# FeatherProto-V3_0.net
KiCad netlist of a schematic drawn in EAGLE
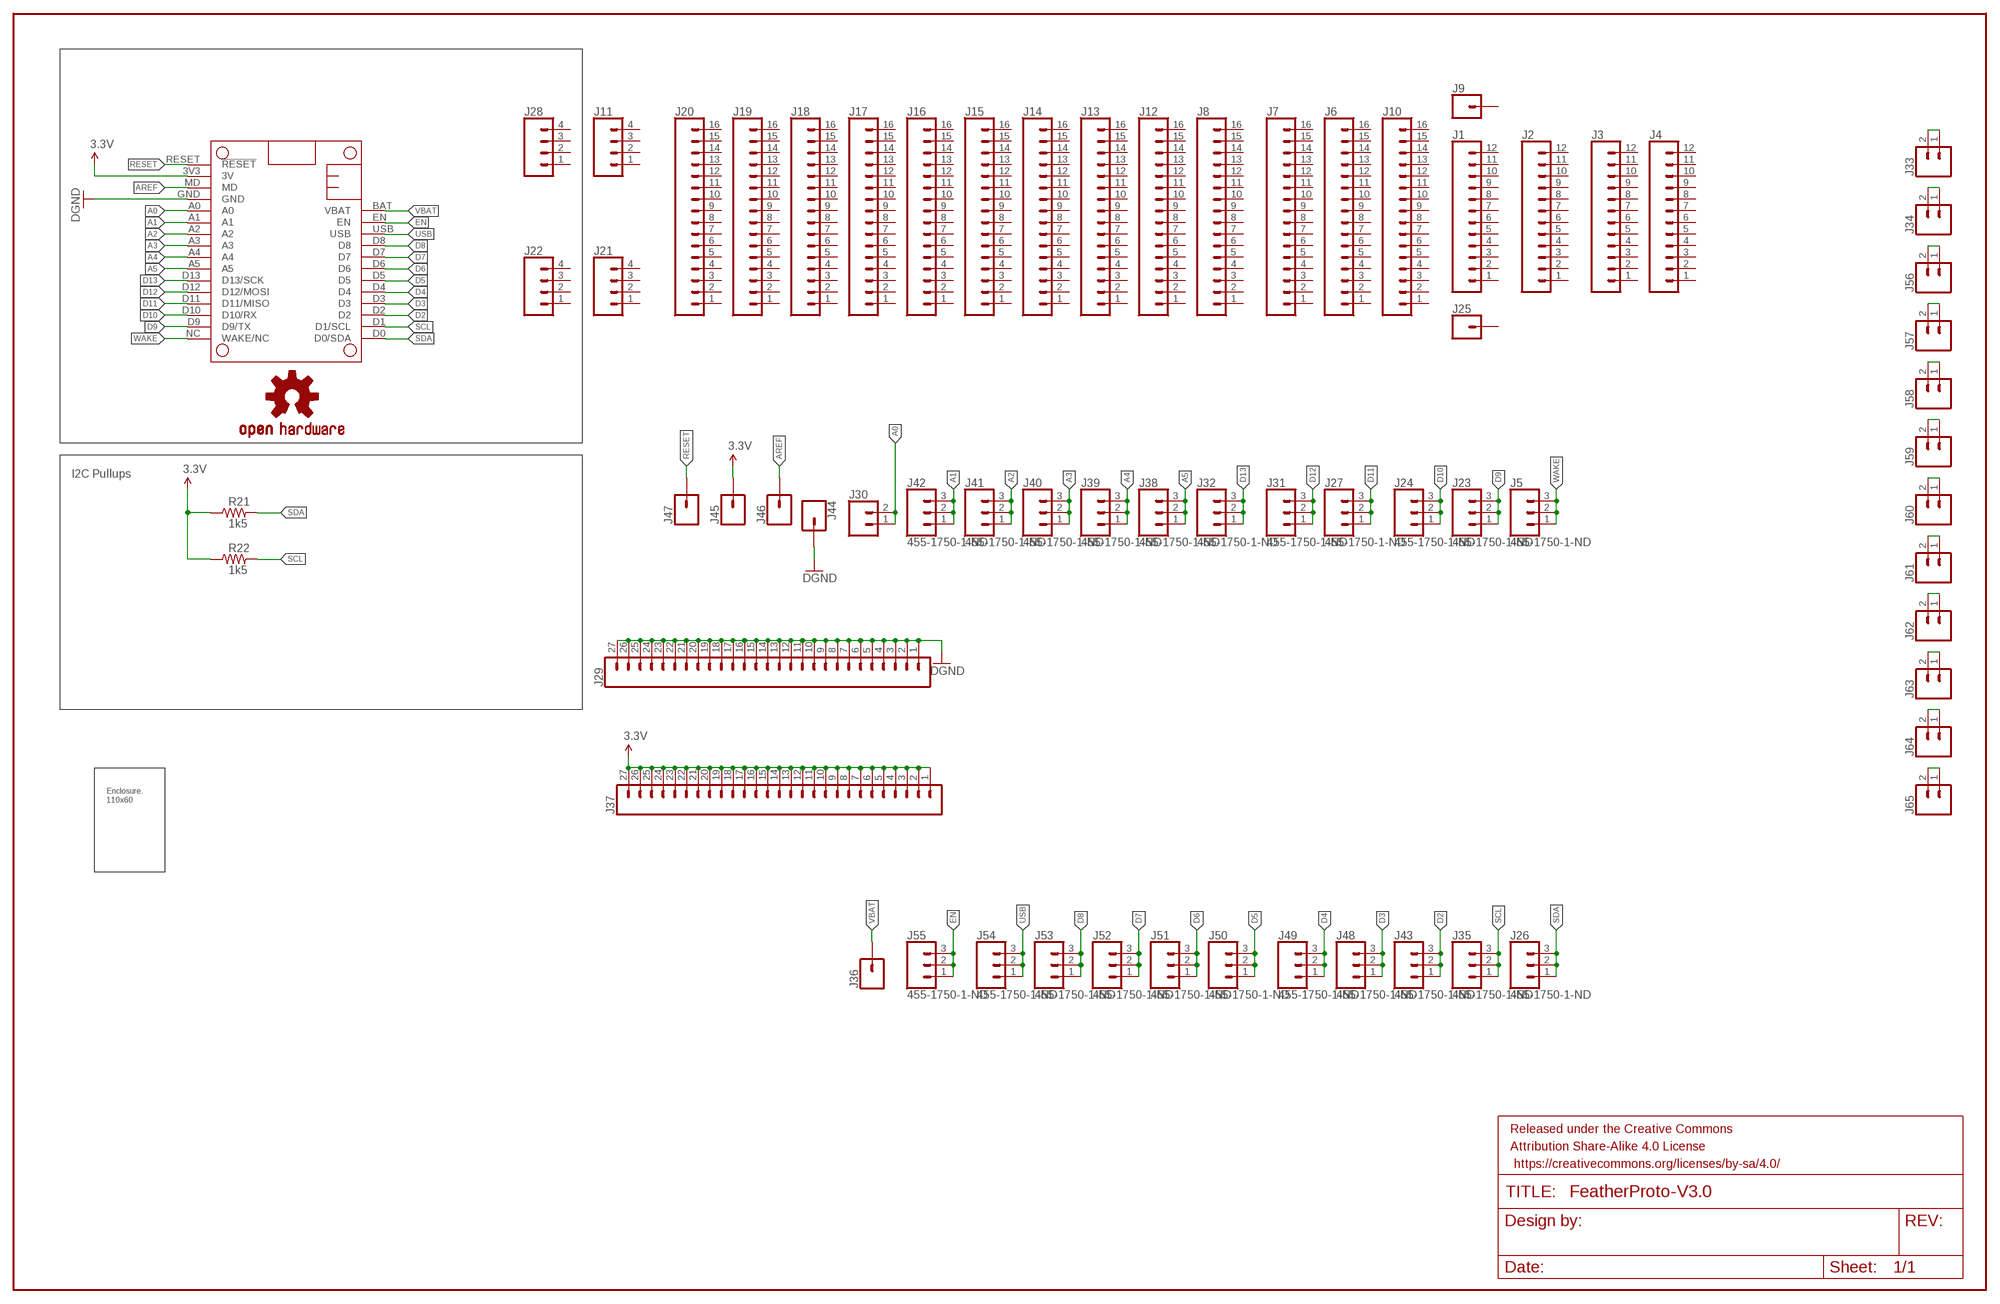
[diagram p0: schematic, sheet 1]

(export (version "E")
  (design (tool "Eeschema 10.0.6"))
  (components
    (comp (ref "FRAME2")
      (value "FRAME-LEDGER")
      (footprint "eagle-import:CREATIVE_COMMONS")
      (libsource (lib "eagle-import") (part "FRAME-LEDGER"))
    )
    (comp (ref "J1")
      (value "CONN_12NO_SILK")
      (footprint "eagle-import:1X12_NO_SILK")
      (libsource (lib "eagle-import") (part "CONN_12NO_SILK"))
    )
    (comp (ref "J2")
      (value "CONN_12NO_SILK")
      (footprint "eagle-import:1X12_NO_SILK")
      (libsource (lib "eagle-import") (part "CONN_12NO_SILK"))
    )
    (comp (ref "J3")
      (value "CONN_12NO_SILK")
      (footprint "eagle-import:1X12_NO_SILK")
      (libsource (lib "eagle-import") (part "CONN_12NO_SILK"))
    )
    (comp (ref "J4")
      (value "CONN_12NO_SILK")
      (footprint "eagle-import:1X12_NO_SILK")
      (libsource (lib "eagle-import") (part "CONN_12NO_SILK"))
    )
    (comp (ref "J5")
      (value "455-1750-1-ND")
      (footprint "eagle-import:1X03")
      (libsource (lib "eagle-import") (part "CONN_03"))
    )
    (comp (ref "J6")
      (value "CONN_161X16_NO_SILK")
      (footprint "eagle-import:1X16_NO_SILK")
      (libsource (lib "eagle-import") (part "CONN_161X16_NO_SILK"))
    )
    (comp (ref "J7")
      (value "CONN_161X16_NO_SILK")
      (footprint "eagle-import:1X16_NO_SILK")
      (libsource (lib "eagle-import") (part "CONN_161X16_NO_SILK"))
    )
    (comp (ref "J8")
      (value "CONN_161X16_NO_SILK")
      (footprint "eagle-import:1X16_NO_SILK")
      (libsource (lib "eagle-import") (part "CONN_161X16_NO_SILK"))
    )
    (comp (ref "J9")
      (value "CONN_01PTH_NO_SILK_YES_STOP")
      (footprint "eagle-import:1X01_NO_SILK")
      (libsource (lib "eagle-import") (part "CONN_01PTH_NO_SILK_YES_STOP"))
    )
    (comp (ref "J10")
      (value "CONN_161X16_NO_SILK")
      (footprint "eagle-import:1X16_NO_SILK")
      (libsource (lib "eagle-import") (part "CONN_161X16_NO_SILK"))
    )
    (comp (ref "J11")
      (value "CONN_041X04_NO_SILK")
      (footprint "eagle-import:1X04_NO_SILK")
      (libsource (lib "eagle-import") (part "CONN_041X04_NO_SILK"))
    )
    (comp (ref "J12")
      (value "CONN_161X16_NO_SILK")
      (footprint "eagle-import:1X16_NO_SILK")
      (libsource (lib "eagle-import") (part "CONN_161X16_NO_SILK"))
    )
    (comp (ref "J13")
      (value "CONN_161X16_NO_SILK")
      (footprint "eagle-import:1X16_NO_SILK")
      (libsource (lib "eagle-import") (part "CONN_161X16_NO_SILK"))
    )
    (comp (ref "J14")
      (value "CONN_161X16_NO_SILK")
      (footprint "eagle-import:1X16_NO_SILK")
      (libsource (lib "eagle-import") (part "CONN_161X16_NO_SILK"))
    )
    (comp (ref "J15")
      (value "CONN_161X16_NO_SILK")
      (footprint "eagle-import:1X16_NO_SILK")
      (libsource (lib "eagle-import") (part "CONN_161X16_NO_SILK"))
    )
    (comp (ref "J16")
      (value "CONN_161X16_NO_SILK")
      (footprint "eagle-import:1X16_NO_SILK")
      (libsource (lib "eagle-import") (part "CONN_161X16_NO_SILK"))
    )
    (comp (ref "J17")
      (value "CONN_161X16_NO_SILK")
      (footprint "eagle-import:1X16_NO_SILK")
      (libsource (lib "eagle-import") (part "CONN_161X16_NO_SILK"))
    )
    (comp (ref "J18")
      (value "CONN_161X16_NO_SILK")
      (footprint "eagle-import:1X16_NO_SILK")
      (libsource (lib "eagle-import") (part "CONN_161X16_NO_SILK"))
    )
    (comp (ref "J19")
      (value "CONN_161X16_NO_SILK")
      (footprint "eagle-import:1X16_NO_SILK")
      (libsource (lib "eagle-import") (part "CONN_161X16_NO_SILK"))
    )
    (comp (ref "J20")
      (value "CONN_161X16_NO_SILK")
      (footprint "eagle-import:1X16_NO_SILK")
      (libsource (lib "eagle-import") (part "CONN_161X16_NO_SILK"))
    )
    (comp (ref "J21")
      (value "CONN_041X04_NO_SILK")
      (footprint "eagle-import:1X04_NO_SILK")
      (libsource (lib "eagle-import") (part "CONN_041X04_NO_SILK"))
    )
    (comp (ref "J22")
      (value "CONN_041X04_NO_SILK")
      (footprint "eagle-import:1X04_NO_SILK")
      (libsource (lib "eagle-import") (part "CONN_041X04_NO_SILK"))
    )
    (comp (ref "J23")
      (value "455-1750-1-ND")
      (footprint "eagle-import:1X03")
      (libsource (lib "eagle-import") (part "CONN_03"))
    )
    (comp (ref "J24")
      (value "455-1750-1-ND")
      (footprint "eagle-import:1X03")
      (libsource (lib "eagle-import") (part "CONN_03"))
    )
    (comp (ref "J25")
      (value "CONN_01PTH_NO_SILK_YES_STOP")
      (footprint "eagle-import:1X01_NO_SILK")
      (libsource (lib "eagle-import") (part "CONN_01PTH_NO_SILK_YES_STOP"))
    )
    (comp (ref "J26")
      (value "455-1750-1-ND")
      (footprint "eagle-import:1X03")
      (libsource (lib "eagle-import") (part "CONN_03"))
    )
    (comp (ref "J27")
      (value "455-1750-1-ND")
      (footprint "eagle-import:1X03")
      (libsource (lib "eagle-import") (part "CONN_03"))
    )
    (comp (ref "J28")
      (value "CONN_041X04_NO_SILK")
      (footprint "eagle-import:1X04_NO_SILK")
      (libsource (lib "eagle-import") (part "CONN_041X04_NO_SILK"))
    )
    (comp (ref "J29")
      (value "CONN_27")
      (footprint "eagle-import:1X27")
      (libsource (lib "eagle-import") (part "CONN_27"))
    )
    (comp (ref "J30")
      (value "CONN_02")
      (footprint "eagle-import:1X02")
      (libsource (lib "eagle-import") (part "CONN_02"))
    )
    (comp (ref "J31")
      (value "455-1750-1-ND")
      (footprint "eagle-import:1X03")
      (libsource (lib "eagle-import") (part "CONN_03"))
    )
    (comp (ref "J32")
      (value "455-1750-1-ND")
      (footprint "eagle-import:1X03")
      (libsource (lib "eagle-import") (part "CONN_03"))
    )
    (comp (ref "J33")
      (value "CONN_02")
      (footprint "eagle-import:1X02")
      (libsource (lib "eagle-import") (part "CONN_02"))
    )
    (comp (ref "J34")
      (value "CONN_02")
      (footprint "eagle-import:1X02")
      (libsource (lib "eagle-import") (part "CONN_02"))
    )
    (comp (ref "J35")
      (value "455-1750-1-ND")
      (footprint "eagle-import:1X03")
      (libsource (lib "eagle-import") (part "CONN_03"))
    )
    (comp (ref "J36")
      (value "CONN_01PTH_NO_SILK_YES_STOP")
      (footprint "eagle-import:1X01_NO_SILK")
      (libsource (lib "eagle-import") (part "CONN_01PTH_NO_SILK_YES_STOP"))
    )
    (comp (ref "J37")
      (value "CONN_27")
      (footprint "eagle-import:1X27")
      (libsource (lib "eagle-import") (part "CONN_27"))
    )
    (comp (ref "J38")
      (value "455-1750-1-ND")
      (footprint "eagle-import:1X03")
      (libsource (lib "eagle-import") (part "CONN_03"))
    )
    (comp (ref "J39")
      (value "455-1750-1-ND")
      (footprint "eagle-import:1X03")
      (libsource (lib "eagle-import") (part "CONN_03"))
    )
    (comp (ref "J40")
      (value "455-1750-1-ND")
      (footprint "eagle-import:1X03")
      (libsource (lib "eagle-import") (part "CONN_03"))
    )
    (comp (ref "J41")
      (value "455-1750-1-ND")
      (footprint "eagle-import:1X03")
      (libsource (lib "eagle-import") (part "CONN_03"))
    )
    (comp (ref "J42")
      (value "455-1750-1-ND")
      (footprint "eagle-import:1X03")
      (libsource (lib "eagle-import") (part "CONN_03"))
    )
    (comp (ref "J43")
      (value "455-1750-1-ND")
      (footprint "eagle-import:1X03")
      (libsource (lib "eagle-import") (part "CONN_03"))
    )
    (comp (ref "J44")
      (value "CONN_01PTH_NO_SILK_YES_STOP")
      (footprint "eagle-import:1X01_NO_SILK")
      (libsource (lib "eagle-import") (part "CONN_01PTH_NO_SILK_YES_STOP"))
    )
    (comp (ref "J45")
      (value "CONN_01PTH_NO_SILK_YES_STOP")
      (footprint "eagle-import:1X01_NO_SILK")
      (libsource (lib "eagle-import") (part "CONN_01PTH_NO_SILK_YES_STOP"))
    )
    (comp (ref "J46")
      (value "CONN_01PTH_NO_SILK_YES_STOP")
      (footprint "eagle-import:1X01_NO_SILK")
      (libsource (lib "eagle-import") (part "CONN_01PTH_NO_SILK_YES_STOP"))
    )
    (comp (ref "J47")
      (value "CONN_01PTH_NO_SILK_YES_STOP")
      (footprint "eagle-import:1X01_NO_SILK")
      (libsource (lib "eagle-import") (part "CONN_01PTH_NO_SILK_YES_STOP"))
    )
    (comp (ref "J48")
      (value "455-1750-1-ND")
      (footprint "eagle-import:1X03")
      (libsource (lib "eagle-import") (part "CONN_03"))
    )
    (comp (ref "J49")
      (value "455-1750-1-ND")
      (footprint "eagle-import:1X03")
      (libsource (lib "eagle-import") (part "CONN_03"))
    )
    (comp (ref "J50")
      (value "455-1750-1-ND")
      (footprint "eagle-import:1X03")
      (libsource (lib "eagle-import") (part "CONN_03"))
    )
    (comp (ref "J51")
      (value "455-1750-1-ND")
      (footprint "eagle-import:1X03")
      (libsource (lib "eagle-import") (part "CONN_03"))
    )
    (comp (ref "J52")
      (value "455-1750-1-ND")
      (footprint "eagle-import:1X03")
      (libsource (lib "eagle-import") (part "CONN_03"))
    )
    (comp (ref "J53")
      (value "455-1750-1-ND")
      (footprint "eagle-import:1X03")
      (libsource (lib "eagle-import") (part "CONN_03"))
    )
    (comp (ref "J54")
      (value "455-1750-1-ND")
      (footprint "eagle-import:1X03")
      (libsource (lib "eagle-import") (part "CONN_03"))
    )
    (comp (ref "J55")
      (value "455-1750-1-ND")
      (footprint "eagle-import:1X03")
      (libsource (lib "eagle-import") (part "CONN_03"))
    )
    (comp (ref "J56")
      (value "CONN_02")
      (footprint "eagle-import:1X02")
      (libsource (lib "eagle-import") (part "CONN_02"))
    )
    (comp (ref "J57")
      (value "CONN_02")
      (footprint "eagle-import:1X02")
      (libsource (lib "eagle-import") (part "CONN_02"))
    )
    (comp (ref "J58")
      (value "CONN_02")
      (footprint "eagle-import:1X02")
      (libsource (lib "eagle-import") (part "CONN_02"))
    )
    (comp (ref "J59")
      (value "CONN_02")
      (footprint "eagle-import:1X02")
      (libsource (lib "eagle-import") (part "CONN_02"))
    )
    (comp (ref "J60")
      (value "CONN_02")
      (footprint "eagle-import:1X02")
      (libsource (lib "eagle-import") (part "CONN_02"))
    )
    (comp (ref "J61")
      (value "CONN_02")
      (footprint "eagle-import:1X02")
      (libsource (lib "eagle-import") (part "CONN_02"))
    )
    (comp (ref "J62")
      (value "CONN_02")
      (footprint "eagle-import:1X02")
      (libsource (lib "eagle-import") (part "CONN_02"))
    )
    (comp (ref "J63")
      (value "CONN_02")
      (footprint "eagle-import:1X02")
      (libsource (lib "eagle-import") (part "CONN_02"))
    )
    (comp (ref "J64")
      (value "CONN_02")
      (footprint "eagle-import:1X02")
      (libsource (lib "eagle-import") (part "CONN_02"))
    )
    (comp (ref "J65")
      (value "CONN_02")
      (footprint "eagle-import:1X02")
      (libsource (lib "eagle-import") (part "CONN_02"))
    )
    (comp (ref "LOGO1")
      (value "OSHW-LOGOM")
      (footprint "eagle-import:OSHW-LOGO-M")
      (libsource (lib "eagle-import") (part "OSHW-LOGOM"))
    )
    (comp (ref "MS1")
      (value "XENONA")
      (footprint "eagle-import:XENON_BREAKOUT_A")
      (libsource (lib "eagle-import") (part "XENONA"))
    )
    (comp (ref "R21")
      (value "1k5")
      (footprint "eagle-import:0805")
      (libsource (lib "eagle-import") (part "RESISTOR0805"))
    )
    (comp (ref "R22")
      (value "1k5")
      (footprint "eagle-import:0805")
      (libsource (lib "eagle-import") (part "RESISTOR0805"))
    )
    (comp (ref "U$1")
      (value "CAMDENBOSS-ENCLOSURE-110X60BOTH-EXTENDED-WIDE")
      (footprint "eagle-import:CAMDENBOSS_ENCLOSURE_110X60_WIDE_EXTENDED")
      (libsource (lib "eagle-import") (part "CAMDENBOSS-ENCLOSURE-110X60BOTH-EXTENDED-WIDE"))
    )
  )
  (nets
    (net (code "1") (name "3.3V") (class "Default")
      (node (ref "J37") (pin "1") (pinfunction "1_1") (pintype "passive"))
      (node (ref "J37") (pin "10") (pinfunction "10_10") (pintype "passive"))
      (node (ref "J37") (pin "11") (pinfunction "11_11") (pintype "passive"))
      (node (ref "J37") (pin "12") (pinfunction "12_12") (pintype "passive"))
      (node (ref "J37") (pin "13") (pinfunction "13_13") (pintype "passive"))
      (node (ref "J37") (pin "14") (pinfunction "14_14") (pintype "passive"))
      (node (ref "J37") (pin "15") (pinfunction "15_15") (pintype "passive"))
      (node (ref "J37") (pin "16") (pinfunction "16_16") (pintype "passive"))
      (node (ref "J37") (pin "17") (pinfunction "17_17") (pintype "passive"))
      (node (ref "J37") (pin "18") (pinfunction "18_18") (pintype "passive"))
      (node (ref "J37") (pin "19") (pinfunction "19_19") (pintype "passive"))
      (node (ref "J37") (pin "2") (pinfunction "2_2") (pintype "passive"))
      (node (ref "J37") (pin "20") (pinfunction "20_20") (pintype "passive"))
      (node (ref "J37") (pin "21") (pinfunction "21_21") (pintype "passive"))
      (node (ref "J37") (pin "22") (pinfunction "22_22") (pintype "passive"))
      (node (ref "J37") (pin "23") (pinfunction "23_23") (pintype "passive"))
      (node (ref "J37") (pin "24") (pinfunction "24_24") (pintype "passive"))
      (node (ref "J37") (pin "25") (pinfunction "25_25") (pintype "passive"))
      (node (ref "J37") (pin "26") (pinfunction "26_26") (pintype "passive"))
      (node (ref "J37") (pin "27") (pinfunction "27_27") (pintype "passive"))
      (node (ref "J37") (pin "3") (pinfunction "3_3") (pintype "passive"))
      (node (ref "J37") (pin "4") (pinfunction "4_4") (pintype "passive"))
      (node (ref "J37") (pin "5") (pinfunction "5_5") (pintype "passive"))
      (node (ref "J37") (pin "6") (pinfunction "6_6") (pintype "passive"))
      (node (ref "J37") (pin "7") (pinfunction "7_7") (pintype "passive"))
      (node (ref "J37") (pin "8") (pinfunction "8_8") (pintype "passive"))
      (node (ref "J37") (pin "9") (pinfunction "9_9") (pintype "passive"))
      (node (ref "J45") (pin "1") (pinfunction "1_1") (pintype "passive"))
      (node (ref "MS1") (pin "3V3") (pinfunction "3V_3V3") (pintype "power_in"))
      (node (ref "R21") (pin "1") (pinfunction "1_1") (pintype "passive"))
      (node (ref "R22") (pin "1") (pinfunction "1_1") (pintype "passive"))
    )
    (net (code "2") (name "A0") (class "Default")
      (node (ref "J30") (pin "1") (pinfunction "1_1") (pintype "passive"))
      (node (ref "J30") (pin "2") (pinfunction "2_2") (pintype "passive"))
      (node (ref "MS1") (pin "A0") (pinfunction "A0_A0") (pintype "bidirectional"))
    )
    (net (code "3") (name "A1") (class "Default")
      (node (ref "J42") (pin "1") (pinfunction "1_1") (pintype "passive"))
      (node (ref "J42") (pin "2") (pinfunction "2_2") (pintype "passive"))
      (node (ref "J42") (pin "3") (pinfunction "3_3") (pintype "passive"))
      (node (ref "MS1") (pin "A1") (pinfunction "A1_A1") (pintype "bidirectional"))
    )
    (net (code "4") (name "A2") (class "Default")
      (node (ref "J41") (pin "1") (pinfunction "1_1") (pintype "passive"))
      (node (ref "J41") (pin "2") (pinfunction "2_2") (pintype "passive"))
      (node (ref "J41") (pin "3") (pinfunction "3_3") (pintype "passive"))
      (node (ref "MS1") (pin "A2") (pinfunction "A2_A2") (pintype "bidirectional"))
    )
    (net (code "5") (name "A3") (class "Default")
      (node (ref "J40") (pin "1") (pinfunction "1_1") (pintype "passive"))
      (node (ref "J40") (pin "2") (pinfunction "2_2") (pintype "passive"))
      (node (ref "J40") (pin "3") (pinfunction "3_3") (pintype "passive"))
      (node (ref "MS1") (pin "A3") (pinfunction "A3_A3") (pintype "bidirectional"))
    )
    (net (code "6") (name "A4") (class "Default")
      (node (ref "J39") (pin "1") (pinfunction "1_1") (pintype "passive"))
      (node (ref "J39") (pin "2") (pinfunction "2_2") (pintype "passive"))
      (node (ref "J39") (pin "3") (pinfunction "3_3") (pintype "passive"))
      (node (ref "MS1") (pin "A4") (pinfunction "A4_A4") (pintype "bidirectional"))
    )
    (net (code "7") (name "A5") (class "Default")
      (node (ref "J38") (pin "1") (pinfunction "1_1") (pintype "passive"))
      (node (ref "J38") (pin "2") (pinfunction "2_2") (pintype "passive"))
      (node (ref "J38") (pin "3") (pinfunction "3_3") (pintype "passive"))
      (node (ref "MS1") (pin "A5") (pinfunction "A5_A5") (pintype "bidirectional"))
    )
    (net (code "8") (name "AREF") (class "Default")
      (node (ref "J46") (pin "1") (pinfunction "1_1") (pintype "passive"))
      (node (ref "MS1") (pin "MD") (pinfunction "MD_MD") (pintype "passive"))
    )
    (net (code "9") (name "D2") (class "Default")
      (node (ref "J43") (pin "1") (pinfunction "1_1") (pintype "passive"))
      (node (ref "J43") (pin "2") (pinfunction "2_2") (pintype "passive"))
      (node (ref "J43") (pin "3") (pinfunction "3_3") (pintype "passive"))
      (node (ref "MS1") (pin "D2") (pinfunction "D2_D2") (pintype "bidirectional"))
    )
    (net (code "10") (name "D3") (class "Default")
      (node (ref "J48") (pin "1") (pinfunction "1_1") (pintype "passive"))
      (node (ref "J48") (pin "2") (pinfunction "2_2") (pintype "passive"))
      (node (ref "J48") (pin "3") (pinfunction "3_3") (pintype "passive"))
      (node (ref "MS1") (pin "D3") (pinfunction "D3_D3") (pintype "bidirectional"))
    )
    (net (code "11") (name "D4") (class "Default")
      (node (ref "J49") (pin "1") (pinfunction "1_1") (pintype "passive"))
      (node (ref "J49") (pin "2") (pinfunction "2_2") (pintype "passive"))
      (node (ref "J49") (pin "3") (pinfunction "3_3") (pintype "passive"))
      (node (ref "MS1") (pin "D4") (pinfunction "D4_D4") (pintype "bidirectional"))
    )
    (net (code "12") (name "D5") (class "Default")
      (node (ref "J50") (pin "1") (pinfunction "1_1") (pintype "passive"))
      (node (ref "J50") (pin "2") (pinfunction "2_2") (pintype "passive"))
      (node (ref "J50") (pin "3") (pinfunction "3_3") (pintype "passive"))
      (node (ref "MS1") (pin "D5") (pinfunction "D5_D5") (pintype "bidirectional"))
    )
    (net (code "13") (name "D6") (class "Default")
      (node (ref "J51") (pin "1") (pinfunction "1_1") (pintype "passive"))
      (node (ref "J51") (pin "2") (pinfunction "2_2") (pintype "passive"))
      (node (ref "J51") (pin "3") (pinfunction "3_3") (pintype "passive"))
      (node (ref "MS1") (pin "D6") (pinfunction "D6_D6") (pintype "bidirectional"))
    )
    (net (code "14") (name "D7") (class "Default")
      (node (ref "J52") (pin "1") (pinfunction "1_1") (pintype "passive"))
      (node (ref "J52") (pin "2") (pinfunction "2_2") (pintype "passive"))
      (node (ref "J52") (pin "3") (pinfunction "3_3") (pintype "passive"))
      (node (ref "MS1") (pin "D7") (pinfunction "D7_D7") (pintype "bidirectional"))
    )
    (net (code "15") (name "D8") (class "Default")
      (node (ref "J53") (pin "1") (pinfunction "1_1") (pintype "passive"))
      (node (ref "J53") (pin "2") (pinfunction "2_2") (pintype "passive"))
      (node (ref "J53") (pin "3") (pinfunction "3_3") (pintype "passive"))
      (node (ref "MS1") (pin "D8") (pinfunction "D8_D8") (pintype "bidirectional"))
    )
    (net (code "16") (name "D9") (class "Default")
      (node (ref "J23") (pin "1") (pinfunction "1_1") (pintype "passive"))
      (node (ref "J23") (pin "2") (pinfunction "2_2") (pintype "passive"))
      (node (ref "J23") (pin "3") (pinfunction "3_3") (pintype "passive"))
      (node (ref "MS1") (pin "D9") (pinfunction "D9/TX_D9") (pintype "bidirectional"))
    )
    (net (code "17") (name "D10") (class "Default")
      (node (ref "J24") (pin "1") (pinfunction "1_1") (pintype "passive"))
      (node (ref "J24") (pin "2") (pinfunction "2_2") (pintype "passive"))
      (node (ref "J24") (pin "3") (pinfunction "3_3") (pintype "passive"))
      (node (ref "MS1") (pin "D10") (pinfunction "D10/RX_D10") (pintype "bidirectional"))
    )
    (net (code "18") (name "D11") (class "Default")
      (node (ref "J27") (pin "1") (pinfunction "1_1") (pintype "passive"))
      (node (ref "J27") (pin "2") (pinfunction "2_2") (pintype "passive"))
      (node (ref "J27") (pin "3") (pinfunction "3_3") (pintype "passive"))
      (node (ref "MS1") (pin "D11") (pinfunction "D11/MISO_D11") (pintype "bidirectional"))
    )
    (net (code "19") (name "D12") (class "Default")
      (node (ref "J31") (pin "1") (pinfunction "1_1") (pintype "passive"))
      (node (ref "J31") (pin "2") (pinfunction "2_2") (pintype "passive"))
      (node (ref "J31") (pin "3") (pinfunction "3_3") (pintype "passive"))
      (node (ref "MS1") (pin "D12") (pinfunction "D12/MOSI_D12") (pintype "bidirectional"))
    )
    (net (code "20") (name "D13") (class "Default")
      (node (ref "J32") (pin "1") (pinfunction "1_1") (pintype "passive"))
      (node (ref "J32") (pin "2") (pinfunction "2_2") (pintype "passive"))
      (node (ref "J32") (pin "3") (pinfunction "3_3") (pintype "passive"))
      (node (ref "MS1") (pin "D13") (pinfunction "D13/SCK_D13") (pintype "bidirectional"))
    )
    (net (code "21") (name "DGND") (class "Default")
      (node (ref "J29") (pin "1") (pinfunction "1_1") (pintype "passive"))
      (node (ref "J29") (pin "10") (pinfunction "10_10") (pintype "passive"))
      (node (ref "J29") (pin "11") (pinfunction "11_11") (pintype "passive"))
      (node (ref "J29") (pin "12") (pinfunction "12_12") (pintype "passive"))
      (node (ref "J29") (pin "13") (pinfunction "13_13") (pintype "passive"))
      (node (ref "J29") (pin "14") (pinfunction "14_14") (pintype "passive"))
      (node (ref "J29") (pin "15") (pinfunction "15_15") (pintype "passive"))
      (node (ref "J29") (pin "16") (pinfunction "16_16") (pintype "passive"))
      (node (ref "J29") (pin "17") (pinfunction "17_17") (pintype "passive"))
      (node (ref "J29") (pin "18") (pinfunction "18_18") (pintype "passive"))
      (node (ref "J29") (pin "19") (pinfunction "19_19") (pintype "passive"))
      (node (ref "J29") (pin "2") (pinfunction "2_2") (pintype "passive"))
      (node (ref "J29") (pin "20") (pinfunction "20_20") (pintype "passive"))
      (node (ref "J29") (pin "21") (pinfunction "21_21") (pintype "passive"))
      (node (ref "J29") (pin "22") (pinfunction "22_22") (pintype "passive"))
      (node (ref "J29") (pin "23") (pinfunction "23_23") (pintype "passive"))
      (node (ref "J29") (pin "24") (pinfunction "24_24") (pintype "passive"))
      (node (ref "J29") (pin "25") (pinfunction "25_25") (pintype "passive"))
      (node (ref "J29") (pin "26") (pinfunction "26_26") (pintype "passive"))
      (node (ref "J29") (pin "27") (pinfunction "27_27") (pintype "passive"))
      (node (ref "J29") (pin "3") (pinfunction "3_3") (pintype "passive"))
      (node (ref "J29") (pin "4") (pinfunction "4_4") (pintype "passive"))
      (node (ref "J29") (pin "5") (pinfunction "5_5") (pintype "passive"))
      (node (ref "J29") (pin "6") (pinfunction "6_6") (pintype "passive"))
      (node (ref "J29") (pin "7") (pinfunction "7_7") (pintype "passive"))
      (node (ref "J29") (pin "8") (pinfunction "8_8") (pintype "passive"))
      (node (ref "J29") (pin "9") (pinfunction "9_9") (pintype "passive"))
      (node (ref "J44") (pin "1") (pinfunction "1_1") (pintype "passive"))
      (node (ref "MS1") (pin "GND") (pinfunction "GND_GND") (pintype "power_in"))
    )
    (net (code "22") (name "EN") (class "Default")
      (node (ref "J55") (pin "1") (pinfunction "1_1") (pintype "passive"))
      (node (ref "J55") (pin "2") (pinfunction "2_2") (pintype "passive"))
      (node (ref "J55") (pin "3") (pinfunction "3_3") (pintype "passive"))
      (node (ref "MS1") (pin "EN") (pinfunction "EN_EN") (pintype "passive"))
    )
    (net (code "23") (name "Net-(J33-Pad1)") (class "Default")
      (node (ref "J33") (pin "1") (pinfunction "1_1") (pintype "passive"))
      (node (ref "J33") (pin "2") (pinfunction "2_2") (pintype "passive"))
    )
    (net (code "24") (name "Net-(J34-Pad1)") (class "Default")
      (node (ref "J34") (pin "1") (pinfunction "1_1") (pintype "passive"))
      (node (ref "J34") (pin "2") (pinfunction "2_2") (pintype "passive"))
    )
    (net (code "25") (name "Net-(J56-Pad1)") (class "Default")
      (node (ref "J56") (pin "1") (pinfunction "1_1") (pintype "passive"))
      (node (ref "J56") (pin "2") (pinfunction "2_2") (pintype "passive"))
    )
    (net (code "26") (name "Net-(J57-Pad1)") (class "Default")
      (node (ref "J57") (pin "1") (pinfunction "1_1") (pintype "passive"))
      (node (ref "J57") (pin "2") (pinfunction "2_2") (pintype "passive"))
    )
    (net (code "27") (name "Net-(J58-Pad1)") (class "Default")
      (node (ref "J58") (pin "1") (pinfunction "1_1") (pintype "passive"))
      (node (ref "J58") (pin "2") (pinfunction "2_2") (pintype "passive"))
    )
    (net (code "28") (name "Net-(J59-Pad1)") (class "Default")
      (node (ref "J59") (pin "1") (pinfunction "1_1") (pintype "passive"))
      (node (ref "J59") (pin "2") (pinfunction "2_2") (pintype "passive"))
    )
    (net (code "29") (name "Net-(J60-Pad1)") (class "Default")
      (node (ref "J60") (pin "1") (pinfunction "1_1") (pintype "passive"))
      (node (ref "J60") (pin "2") (pinfunction "2_2") (pintype "passive"))
    )
    (net (code "30") (name "Net-(J61-Pad1)") (class "Default")
      (node (ref "J61") (pin "1") (pinfunction "1_1") (pintype "passive"))
      (node (ref "J61") (pin "2") (pinfunction "2_2") (pintype "passive"))
    )
    (net (code "31") (name "Net-(J62-Pad1)") (class "Default")
      (node (ref "J62") (pin "1") (pinfunction "1_1") (pintype "passive"))
      (node (ref "J62") (pin "2") (pinfunction "2_2") (pintype "passive"))
    )
    (net (code "32") (name "Net-(J63-Pad1)") (class "Default")
      (node (ref "J63") (pin "1") (pinfunction "1_1") (pintype "passive"))
      (node (ref "J63") (pin "2") (pinfunction "2_2") (pintype "passive"))
    )
    (net (code "33") (name "Net-(J64-Pad1)") (class "Default")
      (node (ref "J64") (pin "1") (pinfunction "1_1") (pintype "passive"))
      (node (ref "J64") (pin "2") (pinfunction "2_2") (pintype "passive"))
    )
    (net (code "34") (name "Net-(J65-Pad1)") (class "Default")
      (node (ref "J65") (pin "1") (pinfunction "1_1") (pintype "passive"))
      (node (ref "J65") (pin "2") (pinfunction "2_2") (pintype "passive"))
    )
    (net (code "35") (name "RESET") (class "Default")
      (node (ref "J47") (pin "1") (pinfunction "1_1") (pintype "passive"))
      (node (ref "MS1") (pin "RESET") (pinfunction "~{RESET}_RESET") (pintype "input"))
    )
    (net (code "36") (name "SCL") (class "Default")
      (node (ref "J35") (pin "1") (pinfunction "1_1") (pintype "passive"))
      (node (ref "J35") (pin "2") (pinfunction "2_2") (pintype "passive"))
      (node (ref "J35") (pin "3") (pinfunction "3_3") (pintype "passive"))
      (node (ref "MS1") (pin "D1") (pinfunction "D1/SCL_D1") (pintype "bidirectional"))
      (node (ref "R22") (pin "2") (pinfunction "2_2") (pintype "passive"))
    )
    (net (code "37") (name "SDA") (class "Default")
      (node (ref "J26") (pin "1") (pinfunction "1_1") (pintype "passive"))
      (node (ref "J26") (pin "2") (pinfunction "2_2") (pintype "passive"))
      (node (ref "J26") (pin "3") (pinfunction "3_3") (pintype "passive"))
      (node (ref "MS1") (pin "D0") (pinfunction "D0/SDA_D0") (pintype "bidirectional"))
      (node (ref "R21") (pin "2") (pinfunction "2_2") (pintype "passive"))
    )
    (net (code "38") (name "USB") (class "Default")
      (node (ref "J54") (pin "1") (pinfunction "1_1") (pintype "passive"))
      (node (ref "J54") (pin "2") (pinfunction "2_2") (pintype "passive"))
      (node (ref "J54") (pin "3") (pinfunction "3_3") (pintype "passive"))
      (node (ref "MS1") (pin "USB") (pinfunction "USB_USB") (pintype "power_in"))
    )
    (net (code "39") (name "VBAT") (class "Default")
      (node (ref "J36") (pin "1") (pinfunction "1_1") (pintype "passive"))
      (node (ref "MS1") (pin "BAT") (pinfunction "VBAT_BAT") (pintype "power_in"))
    )
    (net (code "40") (name "WAKE") (class "Default")
      (node (ref "J5") (pin "1") (pinfunction "1_1") (pintype "passive"))
      (node (ref "J5") (pin "2") (pinfunction "2_2") (pintype "passive"))
      (node (ref "J5") (pin "3") (pinfunction "3_3") (pintype "passive"))
      (node (ref "MS1") (pin "NC") (pinfunction "WAKE/NC_NC") (pintype "passive"))
    )
    (net (code "41") (name "unconnected-(J1-Pad1)") (class "Default")
      (node (ref "J1") (pin "1") (pinfunction "1_1") (pintype "passive"))
    )
    (net (code "42") (name "unconnected-(J1-Pad2)") (class "Default")
      (node (ref "J1") (pin "2") (pinfunction "2_2") (pintype "passive"))
    )
    (net (code "43") (name "unconnected-(J1-Pad3)") (class "Default")
      (node (ref "J1") (pin "3") (pinfunction "3_3") (pintype "passive"))
    )
    (net (code "44") (name "unconnected-(J1-Pad4)") (class "Default")
      (node (ref "J1") (pin "4") (pinfunction "4_4") (pintype "passive"))
    )
    (net (code "45") (name "unconnected-(J1-Pad5)") (class "Default")
      (node (ref "J1") (pin "5") (pinfunction "5_5") (pintype "passive"))
    )
    (net (code "46") (name "unconnected-(J1-Pad6)") (class "Default")
      (node (ref "J1") (pin "6") (pinfunction "6_6") (pintype "passive"))
    )
    (net (code "47") (name "unconnected-(J1-Pad7)") (class "Default")
      (node (ref "J1") (pin "7") (pinfunction "7_7") (pintype "passive"))
    )
    (net (code "48") (name "unconnected-(J1-Pad8)") (class "Default")
      (node (ref "J1") (pin "8") (pinfunction "8_8") (pintype "passive"))
    )
    (net (code "49") (name "unconnected-(J1-Pad9)") (class "Default")
      (node (ref "J1") (pin "9") (pinfunction "9_9") (pintype "passive"))
    )
    (net (code "50") (name "unconnected-(J1-Pad10)") (class "Default")
      (node (ref "J1") (pin "10") (pinfunction "10_10") (pintype "passive"))
    )
    (net (code "51") (name "unconnected-(J1-Pad11)") (class "Default")
      (node (ref "J1") (pin "11") (pinfunction "11_11") (pintype "passive"))
    )
    (net (code "52") (name "unconnected-(J1-Pad12)") (class "Default")
      (node (ref "J1") (pin "12") (pinfunction "12_12") (pintype "passive"))
    )
    (net (code "53") (name "unconnected-(J2-Pad1)") (class "Default")
      (node (ref "J2") (pin "1") (pinfunction "1_1") (pintype "passive"))
    )
    (net (code "54") (name "unconnected-(J2-Pad2)") (class "Default")
      (node (ref "J2") (pin "2") (pinfunction "2_2") (pintype "passive"))
    )
    (net (code "55") (name "unconnected-(J2-Pad3)") (class "Default")
      (node (ref "J2") (pin "3") (pinfunction "3_3") (pintype "passive"))
    )
    (net (code "56") (name "unconnected-(J2-Pad4)") (class "Default")
      (node (ref "J2") (pin "4") (pinfunction "4_4") (pintype "passive"))
    )
    (net (code "57") (name "unconnected-(J2-Pad5)") (class "Default")
      (node (ref "J2") (pin "5") (pinfunction "5_5") (pintype "passive"))
    )
    (net (code "58") (name "unconnected-(J2-Pad6)") (class "Default")
      (node (ref "J2") (pin "6") (pinfunction "6_6") (pintype "passive"))
    )
    (net (code "59") (name "unconnected-(J2-Pad7)") (class "Default")
      (node (ref "J2") (pin "7") (pinfunction "7_7") (pintype "passive"))
    )
    (net (code "60") (name "unconnected-(J2-Pad8)") (class "Default")
      (node (ref "J2") (pin "8") (pinfunction "8_8") (pintype "passive"))
    )
    (net (code "61") (name "unconnected-(J2-Pad9)") (class "Default")
      (node (ref "J2") (pin "9") (pinfunction "9_9") (pintype "passive"))
    )
    (net (code "62") (name "unconnected-(J2-Pad10)") (class "Default")
      (node (ref "J2") (pin "10") (pinfunction "10_10") (pintype "passive"))
    )
    (net (code "63") (name "unconnected-(J2-Pad11)") (class "Default")
      (node (ref "J2") (pin "11") (pinfunction "11_11") (pintype "passive"))
    )
    (net (code "64") (name "unconnected-(J2-Pad12)") (class "Default")
      (node (ref "J2") (pin "12") (pinfunction "12_12") (pintype "passive"))
    )
    (net (code "65") (name "unconnected-(J3-Pad1)") (class "Default")
      (node (ref "J3") (pin "1") (pinfunction "1_1") (pintype "passive"))
    )
    (net (code "66") (name "unconnected-(J3-Pad2)") (class "Default")
      (node (ref "J3") (pin "2") (pinfunction "2_2") (pintype "passive"))
    )
    (net (code "67") (name "unconnected-(J3-Pad3)") (class "Default")
      (node (ref "J3") (pin "3") (pinfunction "3_3") (pintype "passive"))
    )
    (net (code "68") (name "unconnected-(J3-Pad4)") (class "Default")
      (node (ref "J3") (pin "4") (pinfunction "4_4") (pintype "passive"))
    )
    (net (code "69") (name "unconnected-(J3-Pad5)") (class "Default")
      (node (ref "J3") (pin "5") (pinfunction "5_5") (pintype "passive"))
    )
    (net (code "70") (name "unconnected-(J3-Pad6)") (class "Default")
      (node (ref "J3") (pin "6") (pinfunction "6_6") (pintype "passive"))
    )
    (net (code "71") (name "unconnected-(J3-Pad7)") (class "Default")
      (node (ref "J3") (pin "7") (pinfunction "7_7") (pintype "passive"))
    )
    (net (code "72") (name "unconnected-(J3-Pad8)") (class "Default")
      (node (ref "J3") (pin "8") (pinfunction "8_8") (pintype "passive"))
    )
    (net (code "73") (name "unconnected-(J3-Pad9)") (class "Default")
      (node (ref "J3") (pin "9") (pinfunction "9_9") (pintype "passive"))
    )
    (net (code "74") (name "unconnected-(J3-Pad10)") (class "Default")
      (node (ref "J3") (pin "10") (pinfunction "10_10") (pintype "passive"))
    )
    (net (code "75") (name "unconnected-(J3-Pad11)") (class "Default")
      (node (ref "J3") (pin "11") (pinfunction "11_11") (pintype "passive"))
    )
    (net (code "76") (name "unconnected-(J3-Pad12)") (class "Default")
      (node (ref "J3") (pin "12") (pinfunction "12_12") (pintype "passive"))
    )
    (net (code "77") (name "unconnected-(J4-Pad1)") (class "Default")
      (node (ref "J4") (pin "1") (pinfunction "1_1") (pintype "passive"))
    )
    (net (code "78") (name "unconnected-(J4-Pad2)") (class "Default")
      (node (ref "J4") (pin "2") (pinfunction "2_2") (pintype "passive"))
    )
    (net (code "79") (name "unconnected-(J4-Pad3)") (class "Default")
      (node (ref "J4") (pin "3") (pinfunction "3_3") (pintype "passive"))
    )
    (net (code "80") (name "unconnected-(J4-Pad4)") (class "Default")
      (node (ref "J4") (pin "4") (pinfunction "4_4") (pintype "passive"))
    )
    (net (code "81") (name "unconnected-(J4-Pad5)") (class "Default")
      (node (ref "J4") (pin "5") (pinfunction "5_5") (pintype "passive"))
    )
    (net (code "82") (name "unconnected-(J4-Pad6)") (class "Default")
      (node (ref "J4") (pin "6") (pinfunction "6_6") (pintype "passive"))
    )
    (net (code "83") (name "unconnected-(J4-Pad7)") (class "Default")
      (node (ref "J4") (pin "7") (pinfunction "7_7") (pintype "passive"))
    )
    (net (code "84") (name "unconnected-(J4-Pad8)") (class "Default")
      (node (ref "J4") (pin "8") (pinfunction "8_8") (pintype "passive"))
    )
    (net (code "85") (name "unconnected-(J4-Pad9)") (class "Default")
      (node (ref "J4") (pin "9") (pinfunction "9_9") (pintype "passive"))
    )
    (net (code "86") (name "unconnected-(J4-Pad10)") (class "Default")
      (node (ref "J4") (pin "10") (pinfunction "10_10") (pintype "passive"))
    )
    (net (code "87") (name "unconnected-(J4-Pad11)") (class "Default")
      (node (ref "J4") (pin "11") (pinfunction "11_11") (pintype "passive"))
    )
    (net (code "88") (name "unconnected-(J4-Pad12)") (class "Default")
      (node (ref "J4") (pin "12") (pinfunction "12_12") (pintype "passive"))
    )
    (net (code "89") (name "unconnected-(J6-Pad1)") (class "Default")
      (node (ref "J6") (pin "1") (pinfunction "1_1") (pintype "passive"))
    )
    (net (code "90") (name "unconnected-(J6-Pad2)") (class "Default")
      (node (ref "J6") (pin "2") (pinfunction "2_2") (pintype "passive"))
    )
    (net (code "91") (name "unconnected-(J6-Pad3)") (class "Default")
      (node (ref "J6") (pin "3") (pinfunction "3_3") (pintype "passive"))
    )
    (net (code "92") (name "unconnected-(J6-Pad4)") (class "Default")
      (node (ref "J6") (pin "4") (pinfunction "4_4") (pintype "passive"))
    )
    (net (code "93") (name "unconnected-(J6-Pad5)") (class "Default")
      (node (ref "J6") (pin "5") (pinfunction "5_5") (pintype "passive"))
    )
    (net (code "94") (name "unconnected-(J6-Pad6)") (class "Default")
      (node (ref "J6") (pin "6") (pinfunction "6_6") (pintype "passive"))
    )
    (net (code "95") (name "unconnected-(J6-Pad7)") (class "Default")
      (node (ref "J6") (pin "7") (pinfunction "7_7") (pintype "passive"))
    )
    (net (code "96") (name "unconnected-(J6-Pad8)") (class "Default")
      (node (ref "J6") (pin "8") (pinfunction "8_8") (pintype "passive"))
    )
    (net (code "97") (name "unconnected-(J6-Pad9)") (class "Default")
      (node (ref "J6") (pin "9") (pinfunction "9_9") (pintype "passive"))
    )
    (net (code "98") (name "unconnected-(J6-Pad10)") (class "Default")
      (node (ref "J6") (pin "10") (pinfunction "10_10") (pintype "passive"))
    )
    (net (code "99") (name "unconnected-(J6-Pad11)") (class "Default")
      (node (ref "J6") (pin "11") (pinfunction "11_11") (pintype "passive"))
    )
    (net (code "100") (name "unconnected-(J6-Pad12)") (class "Default")
      (node (ref "J6") (pin "12") (pinfunction "12_12") (pintype "passive"))
    )
    (net (code "101") (name "unconnected-(J6-Pad13)") (class "Default")
      (node (ref "J6") (pin "13") (pinfunction "13_13") (pintype "passive"))
    )
    (net (code "102") (name "unconnected-(J6-Pad14)") (class "Default")
      (node (ref "J6") (pin "14") (pinfunction "14_14") (pintype "passive"))
    )
    (net (code "103") (name "unconnected-(J6-Pad15)") (class "Default")
      (node (ref "J6") (pin "15") (pinfunction "15_15") (pintype "passive"))
    )
    (net (code "104") (name "unconnected-(J6-Pad16)") (class "Default")
      (node (ref "J6") (pin "16") (pinfunction "16_16") (pintype "passive"))
    )
    (net (code "105") (name "unconnected-(J7-Pad1)") (class "Default")
      (node (ref "J7") (pin "1") (pinfunction "1_1") (pintype "passive"))
    )
    (net (code "106") (name "unconnected-(J7-Pad2)") (class "Default")
      (node (ref "J7") (pin "2") (pinfunction "2_2") (pintype "passive"))
    )
    (net (code "107") (name "unconnected-(J7-Pad3)") (class "Default")
      (node (ref "J7") (pin "3") (pinfunction "3_3") (pintype "passive"))
    )
    (net (code "108") (name "unconnected-(J7-Pad4)") (class "Default")
      (node (ref "J7") (pin "4") (pinfunction "4_4") (pintype "passive"))
    )
    (net (code "109") (name "unconnected-(J7-Pad5)") (class "Default")
      (node (ref "J7") (pin "5") (pinfunction "5_5") (pintype "passive"))
    )
    (net (code "110") (name "unconnected-(J7-Pad6)") (class "Default")
      (node (ref "J7") (pin "6") (pinfunction "6_6") (pintype "passive"))
    )
    (net (code "111") (name "unconnected-(J7-Pad7)") (class "Default")
      (node (ref "J7") (pin "7") (pinfunction "7_7") (pintype "passive"))
    )
    (net (code "112") (name "unconnected-(J7-Pad8)") (class "Default")
      (node (ref "J7") (pin "8") (pinfunction "8_8") (pintype "passive"))
    )
    (net (code "113") (name "unconnected-(J7-Pad9)") (class "Default")
      (node (ref "J7") (pin "9") (pinfunction "9_9") (pintype "passive"))
    )
    (net (code "114") (name "unconnected-(J7-Pad10)") (class "Default")
      (node (ref "J7") (pin "10") (pinfunction "10_10") (pintype "passive"))
    )
    (net (code "115") (name "unconnected-(J7-Pad11)") (class "Default")
      (node (ref "J7") (pin "11") (pinfunction "11_11") (pintype "passive"))
    )
    (net (code "116") (name "unconnected-(J7-Pad12)") (class "Default")
      (node (ref "J7") (pin "12") (pinfunction "12_12") (pintype "passive"))
    )
    (net (code "117") (name "unconnected-(J7-Pad13)") (class "Default")
      (node (ref "J7") (pin "13") (pinfunction "13_13") (pintype "passive"))
    )
    (net (code "118") (name "unconnected-(J7-Pad14)") (class "Default")
      (node (ref "J7") (pin "14") (pinfunction "14_14") (pintype "passive"))
    )
    (net (code "119") (name "unconnected-(J7-Pad15)") (class "Default")
      (node (ref "J7") (pin "15") (pinfunction "15_15") (pintype "passive"))
    )
    (net (code "120") (name "unconnected-(J7-Pad16)") (class "Default")
      (node (ref "J7") (pin "16") (pinfunction "16_16") (pintype "passive"))
    )
    (net (code "121") (name "unconnected-(J8-Pad1)") (class "Default")
      (node (ref "J8") (pin "1") (pinfunction "1_1") (pintype "passive"))
    )
    (net (code "122") (name "unconnected-(J8-Pad2)") (class "Default")
      (node (ref "J8") (pin "2") (pinfunction "2_2") (pintype "passive"))
    )
    (net (code "123") (name "unconnected-(J8-Pad3)") (class "Default")
      (node (ref "J8") (pin "3") (pinfunction "3_3") (pintype "passive"))
    )
    (net (code "124") (name "unconnected-(J8-Pad4)") (class "Default")
      (node (ref "J8") (pin "4") (pinfunction "4_4") (pintype "passive"))
    )
    (net (code "125") (name "unconnected-(J8-Pad5)") (class "Default")
      (node (ref "J8") (pin "5") (pinfunction "5_5") (pintype "passive"))
    )
    (net (code "126") (name "unconnected-(J8-Pad6)") (class "Default")
      (node (ref "J8") (pin "6") (pinfunction "6_6") (pintype "passive"))
    )
    (net (code "127") (name "unconnected-(J8-Pad7)") (class "Default")
      (node (ref "J8") (pin "7") (pinfunction "7_7") (pintype "passive"))
    )
    (net (code "128") (name "unconnected-(J8-Pad8)") (class "Default")
      (node (ref "J8") (pin "8") (pinfunction "8_8") (pintype "passive"))
    )
    (net (code "129") (name "unconnected-(J8-Pad9)") (class "Default")
      (node (ref "J8") (pin "9") (pinfunction "9_9") (pintype "passive"))
    )
    (net (code "130") (name "unconnected-(J8-Pad10)") (class "Default")
      (node (ref "J8") (pin "10") (pinfunction "10_10") (pintype "passive"))
    )
    (net (code "131") (name "unconnected-(J8-Pad11)") (class "Default")
      (node (ref "J8") (pin "11") (pinfunction "11_11") (pintype "passive"))
    )
    (net (code "132") (name "unconnected-(J8-Pad12)") (class "Default")
      (node (ref "J8") (pin "12") (pinfunction "12_12") (pintype "passive"))
    )
    (net (code "133") (name "unconnected-(J8-Pad13)") (class "Default")
      (node (ref "J8") (pin "13") (pinfunction "13_13") (pintype "passive"))
    )
    (net (code "134") (name "unconnected-(J8-Pad14)") (class "Default")
      (node (ref "J8") (pin "14") (pinfunction "14_14") (pintype "passive"))
    )
    (net (code "135") (name "unconnected-(J8-Pad15)") (class "Default")
      (node (ref "J8") (pin "15") (pinfunction "15_15") (pintype "passive"))
    )
    (net (code "136") (name "unconnected-(J8-Pad16)") (class "Default")
      (node (ref "J8") (pin "16") (pinfunction "16_16") (pintype "passive"))
    )
    (net (code "137") (name "unconnected-(J9-Pad1)") (class "Default")
      (node (ref "J9") (pin "1") (pinfunction "1_1") (pintype "passive"))
    )
    (net (code "138") (name "unconnected-(J10-Pad1)") (class "Default")
      (node (ref "J10") (pin "1") (pinfunction "1_1") (pintype "passive"))
    )
    (net (code "139") (name "unconnected-(J10-Pad2)") (class "Default")
      (node (ref "J10") (pin "2") (pinfunction "2_2") (pintype "passive"))
    )
    (net (code "140") (name "unconnected-(J10-Pad3)") (class "Default")
      (node (ref "J10") (pin "3") (pinfunction "3_3") (pintype "passive"))
    )
    (net (code "141") (name "unconnected-(J10-Pad4)") (class "Default")
      (node (ref "J10") (pin "4") (pinfunction "4_4") (pintype "passive"))
    )
    (net (code "142") (name "unconnected-(J10-Pad5)") (class "Default")
      (node (ref "J10") (pin "5") (pinfunction "5_5") (pintype "passive"))
    )
    (net (code "143") (name "unconnected-(J10-Pad6)") (class "Default")
      (node (ref "J10") (pin "6") (pinfunction "6_6") (pintype "passive"))
    )
    (net (code "144") (name "unconnected-(J10-Pad7)") (class "Default")
      (node (ref "J10") (pin "7") (pinfunction "7_7") (pintype "passive"))
    )
    (net (code "145") (name "unconnected-(J10-Pad8)") (class "Default")
      (node (ref "J10") (pin "8") (pinfunction "8_8") (pintype "passive"))
    )
    (net (code "146") (name "unconnected-(J10-Pad9)") (class "Default")
      (node (ref "J10") (pin "9") (pinfunction "9_9") (pintype "passive"))
    )
    (net (code "147") (name "unconnected-(J10-Pad10)") (class "Default")
      (node (ref "J10") (pin "10") (pinfunction "10_10") (pintype "passive"))
    )
    (net (code "148") (name "unconnected-(J10-Pad11)") (class "Default")
      (node (ref "J10") (pin "11") (pinfunction "11_11") (pintype "passive"))
    )
    (net (code "149") (name "unconnected-(J10-Pad12)") (class "Default")
      (node (ref "J10") (pin "12") (pinfunction "12_12") (pintype "passive"))
    )
    (net (code "150") (name "unconnected-(J10-Pad13)") (class "Default")
      (node (ref "J10") (pin "13") (pinfunction "13_13") (pintype "passive"))
    )
    (net (code "151") (name "unconnected-(J10-Pad14)") (class "Default")
      (node (ref "J10") (pin "14") (pinfunction "14_14") (pintype "passive"))
    )
    (net (code "152") (name "unconnected-(J10-Pad15)") (class "Default")
      (node (ref "J10") (pin "15") (pinfunction "15_15") (pintype "passive"))
    )
    (net (code "153") (name "unconnected-(J10-Pad16)") (class "Default")
      (node (ref "J10") (pin "16") (pinfunction "16_16") (pintype "passive"))
    )
    (net (code "154") (name "unconnected-(J11-Pad1)") (class "Default")
      (node (ref "J11") (pin "1") (pinfunction "1_1") (pintype "passive"))
    )
    (net (code "155") (name "unconnected-(J11-Pad2)") (class "Default")
      (node (ref "J11") (pin "2") (pinfunction "2_2") (pintype "passive"))
    )
    (net (code "156") (name "unconnected-(J11-Pad3)") (class "Default")
      (node (ref "J11") (pin "3") (pinfunction "3_3") (pintype "passive"))
    )
    (net (code "157") (name "unconnected-(J11-Pad4)") (class "Default")
      (node (ref "J11") (pin "4") (pinfunction "4_4") (pintype "passive"))
    )
    (net (code "158") (name "unconnected-(J12-Pad1)") (class "Default")
      (node (ref "J12") (pin "1") (pinfunction "1_1") (pintype "passive"))
    )
    (net (code "159") (name "unconnected-(J12-Pad2)") (class "Default")
      (node (ref "J12") (pin "2") (pinfunction "2_2") (pintype "passive"))
    )
    (net (code "160") (name "unconnected-(J12-Pad3)") (class "Default")
      (node (ref "J12") (pin "3") (pinfunction "3_3") (pintype "passive"))
    )
    (net (code "161") (name "unconnected-(J12-Pad4)") (class "Default")
      (node (ref "J12") (pin "4") (pinfunction "4_4") (pintype "passive"))
    )
    (net (code "162") (name "unconnected-(J12-Pad5)") (class "Default")
      (node (ref "J12") (pin "5") (pinfunction "5_5") (pintype "passive"))
    )
    (net (code "163") (name "unconnected-(J12-Pad6)") (class "Default")
      (node (ref "J12") (pin "6") (pinfunction "6_6") (pintype "passive"))
    )
    (net (code "164") (name "unconnected-(J12-Pad7)") (class "Default")
      (node (ref "J12") (pin "7") (pinfunction "7_7") (pintype "passive"))
    )
    (net (code "165") (name "unconnected-(J12-Pad8)") (class "Default")
      (node (ref "J12") (pin "8") (pinfunction "8_8") (pintype "passive"))
    )
    (net (code "166") (name "unconnected-(J12-Pad9)") (class "Default")
      (node (ref "J12") (pin "9") (pinfunction "9_9") (pintype "passive"))
    )
    (net (code "167") (name "unconnected-(J12-Pad10)") (class "Default")
      (node (ref "J12") (pin "10") (pinfunction "10_10") (pintype "passive"))
    )
    (net (code "168") (name "unconnected-(J12-Pad11)") (class "Default")
      (node (ref "J12") (pin "11") (pinfunction "11_11") (pintype "passive"))
    )
    (net (code "169") (name "unconnected-(J12-Pad12)") (class "Default")
      (node (ref "J12") (pin "12") (pinfunction "12_12") (pintype "passive"))
    )
    (net (code "170") (name "unconnected-(J12-Pad13)") (class "Default")
      (node (ref "J12") (pin "13") (pinfunction "13_13") (pintype "passive"))
    )
    (net (code "171") (name "unconnected-(J12-Pad14)") (class "Default")
      (node (ref "J12") (pin "14") (pinfunction "14_14") (pintype "passive"))
    )
    (net (code "172") (name "unconnected-(J12-Pad15)") (class "Default")
      (node (ref "J12") (pin "15") (pinfunction "15_15") (pintype "passive"))
    )
    (net (code "173") (name "unconnected-(J12-Pad16)") (class "Default")
      (node (ref "J12") (pin "16") (pinfunction "16_16") (pintype "passive"))
    )
    (net (code "174") (name "unconnected-(J13-Pad1)") (class "Default")
      (node (ref "J13") (pin "1") (pinfunction "1_1") (pintype "passive"))
    )
    (net (code "175") (name "unconnected-(J13-Pad2)") (class "Default")
      (node (ref "J13") (pin "2") (pinfunction "2_2") (pintype "passive"))
    )
    (net (code "176") (name "unconnected-(J13-Pad3)") (class "Default")
      (node (ref "J13") (pin "3") (pinfunction "3_3") (pintype "passive"))
    )
    (net (code "177") (name "unconnected-(J13-Pad4)") (class "Default")
      (node (ref "J13") (pin "4") (pinfunction "4_4") (pintype "passive"))
    )
    (net (code "178") (name "unconnected-(J13-Pad5)") (class "Default")
      (node (ref "J13") (pin "5") (pinfunction "5_5") (pintype "passive"))
    )
    (net (code "179") (name "unconnected-(J13-Pad6)") (class "Default")
      (node (ref "J13") (pin "6") (pinfunction "6_6") (pintype "passive"))
    )
    (net (code "180") (name "unconnected-(J13-Pad7)") (class "Default")
      (node (ref "J13") (pin "7") (pinfunction "7_7") (pintype "passive"))
    )
    (net (code "181") (name "unconnected-(J13-Pad8)") (class "Default")
      (node (ref "J13") (pin "8") (pinfunction "8_8") (pintype "passive"))
    )
    (net (code "182") (name "unconnected-(J13-Pad9)") (class "Default")
      (node (ref "J13") (pin "9") (pinfunction "9_9") (pintype "passive"))
    )
    (net (code "183") (name "unconnected-(J13-Pad10)") (class "Default")
      (node (ref "J13") (pin "10") (pinfunction "10_10") (pintype "passive"))
    )
    (net (code "184") (name "unconnected-(J13-Pad11)") (class "Default")
      (node (ref "J13") (pin "11") (pinfunction "11_11") (pintype "passive"))
    )
    (net (code "185") (name "unconnected-(J13-Pad12)") (class "Default")
      (node (ref "J13") (pin "12") (pinfunction "12_12") (pintype "passive"))
    )
    (net (code "186") (name "unconnected-(J13-Pad13)") (class "Default")
      (node (ref "J13") (pin "13") (pinfunction "13_13") (pintype "passive"))
    )
    (net (code "187") (name "unconnected-(J13-Pad14)") (class "Default")
      (node (ref "J13") (pin "14") (pinfunction "14_14") (pintype "passive"))
    )
    (net (code "188") (name "unconnected-(J13-Pad15)") (class "Default")
      (node (ref "J13") (pin "15") (pinfunction "15_15") (pintype "passive"))
    )
    (net (code "189") (name "unconnected-(J13-Pad16)") (class "Default")
      (node (ref "J13") (pin "16") (pinfunction "16_16") (pintype "passive"))
    )
    (net (code "190") (name "unconnected-(J14-Pad1)") (class "Default")
      (node (ref "J14") (pin "1") (pinfunction "1_1") (pintype "passive"))
    )
    (net (code "191") (name "unconnected-(J14-Pad2)") (class "Default")
      (node (ref "J14") (pin "2") (pinfunction "2_2") (pintype "passive"))
    )
    (net (code "192") (name "unconnected-(J14-Pad3)") (class "Default")
      (node (ref "J14") (pin "3") (pinfunction "3_3") (pintype "passive"))
    )
    (net (code "193") (name "unconnected-(J14-Pad4)") (class "Default")
      (node (ref "J14") (pin "4") (pinfunction "4_4") (pintype "passive"))
    )
    (net (code "194") (name "unconnected-(J14-Pad5)") (class "Default")
      (node (ref "J14") (pin "5") (pinfunction "5_5") (pintype "passive"))
    )
    (net (code "195") (name "unconnected-(J14-Pad6)") (class "Default")
      (node (ref "J14") (pin "6") (pinfunction "6_6") (pintype "passive"))
    )
    (net (code "196") (name "unconnected-(J14-Pad7)") (class "Default")
      (node (ref "J14") (pin "7") (pinfunction "7_7") (pintype "passive"))
    )
    (net (code "197") (name "unconnected-(J14-Pad8)") (class "Default")
      (node (ref "J14") (pin "8") (pinfunction "8_8") (pintype "passive"))
    )
    (net (code "198") (name "unconnected-(J14-Pad9)") (class "Default")
      (node (ref "J14") (pin "9") (pinfunction "9_9") (pintype "passive"))
    )
    (net (code "199") (name "unconnected-(J14-Pad10)") (class "Default")
      (node (ref "J14") (pin "10") (pinfunction "10_10") (pintype "passive"))
    )
    (net (code "200") (name "unconnected-(J14-Pad11)") (class "Default")
      (node (ref "J14") (pin "11") (pinfunction "11_11") (pintype "passive"))
    )
    (net (code "201") (name "unconnected-(J14-Pad12)") (class "Default")
      (node (ref "J14") (pin "12") (pinfunction "12_12") (pintype "passive"))
    )
    (net (code "202") (name "unconnected-(J14-Pad13)") (class "Default")
      (node (ref "J14") (pin "13") (pinfunction "13_13") (pintype "passive"))
    )
    (net (code "203") (name "unconnected-(J14-Pad14)") (class "Default")
      (node (ref "J14") (pin "14") (pinfunction "14_14") (pintype "passive"))
    )
    (net (code "204") (name "unconnected-(J14-Pad15)") (class "Default")
      (node (ref "J14") (pin "15") (pinfunction "15_15") (pintype "passive"))
    )
    (net (code "205") (name "unconnected-(J14-Pad16)") (class "Default")
      (node (ref "J14") (pin "16") (pinfunction "16_16") (pintype "passive"))
    )
    (net (code "206") (name "unconnected-(J15-Pad1)") (class "Default")
      (node (ref "J15") (pin "1") (pinfunction "1_1") (pintype "passive"))
    )
    (net (code "207") (name "unconnected-(J15-Pad2)") (class "Default")
      (node (ref "J15") (pin "2") (pinfunction "2_2") (pintype "passive"))
    )
    (net (code "208") (name "unconnected-(J15-Pad3)") (class "Default")
      (node (ref "J15") (pin "3") (pinfunction "3_3") (pintype "passive"))
    )
    (net (code "209") (name "unconnected-(J15-Pad4)") (class "Default")
      (node (ref "J15") (pin "4") (pinfunction "4_4") (pintype "passive"))
    )
    (net (code "210") (name "unconnected-(J15-Pad5)") (class "Default")
      (node (ref "J15") (pin "5") (pinfunction "5_5") (pintype "passive"))
    )
    (net (code "211") (name "unconnected-(J15-Pad6)") (class "Default")
      (node (ref "J15") (pin "6") (pinfunction "6_6") (pintype "passive"))
    )
    (net (code "212") (name "unconnected-(J15-Pad7)") (class "Default")
      (node (ref "J15") (pin "7") (pinfunction "7_7") (pintype "passive"))
    )
    (net (code "213") (name "unconnected-(J15-Pad8)") (class "Default")
      (node (ref "J15") (pin "8") (pinfunction "8_8") (pintype "passive"))
    )
    (net (code "214") (name "unconnected-(J15-Pad9)") (class "Default")
      (node (ref "J15") (pin "9") (pinfunction "9_9") (pintype "passive"))
    )
    (net (code "215") (name "unconnected-(J15-Pad10)") (class "Default")
      (node (ref "J15") (pin "10") (pinfunction "10_10") (pintype "passive"))
    )
    (net (code "216") (name "unconnected-(J15-Pad11)") (class "Default")
      (node (ref "J15") (pin "11") (pinfunction "11_11") (pintype "passive"))
    )
    (net (code "217") (name "unconnected-(J15-Pad12)") (class "Default")
      (node (ref "J15") (pin "12") (pinfunction "12_12") (pintype "passive"))
    )
    (net (code "218") (name "unconnected-(J15-Pad13)") (class "Default")
      (node (ref "J15") (pin "13") (pinfunction "13_13") (pintype "passive"))
    )
    (net (code "219") (name "unconnected-(J15-Pad14)") (class "Default")
      (node (ref "J15") (pin "14") (pinfunction "14_14") (pintype "passive"))
    )
    (net (code "220") (name "unconnected-(J15-Pad15)") (class "Default")
      (node (ref "J15") (pin "15") (pinfunction "15_15") (pintype "passive"))
    )
    (net (code "221") (name "unconnected-(J15-Pad16)") (class "Default")
      (node (ref "J15") (pin "16") (pinfunction "16_16") (pintype "passive"))
    )
    (net (code "222") (name "unconnected-(J16-Pad1)") (class "Default")
      (node (ref "J16") (pin "1") (pinfunction "1_1") (pintype "passive"))
    )
    (net (code "223") (name "unconnected-(J16-Pad2)") (class "Default")
      (node (ref "J16") (pin "2") (pinfunction "2_2") (pintype "passive"))
    )
    (net (code "224") (name "unconnected-(J16-Pad3)") (class "Default")
      (node (ref "J16") (pin "3") (pinfunction "3_3") (pintype "passive"))
    )
    (net (code "225") (name "unconnected-(J16-Pad4)") (class "Default")
      (node (ref "J16") (pin "4") (pinfunction "4_4") (pintype "passive"))
    )
    (net (code "226") (name "unconnected-(J16-Pad5)") (class "Default")
      (node (ref "J16") (pin "5") (pinfunction "5_5") (pintype "passive"))
    )
    (net (code "227") (name "unconnected-(J16-Pad6)") (class "Default")
      (node (ref "J16") (pin "6") (pinfunction "6_6") (pintype "passive"))
    )
    (net (code "228") (name "unconnected-(J16-Pad7)") (class "Default")
      (node (ref "J16") (pin "7") (pinfunction "7_7") (pintype "passive"))
    )
    (net (code "229") (name "unconnected-(J16-Pad8)") (class "Default")
      (node (ref "J16") (pin "8") (pinfunction "8_8") (pintype "passive"))
    )
    (net (code "230") (name "unconnected-(J16-Pad9)") (class "Default")
      (node (ref "J16") (pin "9") (pinfunction "9_9") (pintype "passive"))
    )
    (net (code "231") (name "unconnected-(J16-Pad10)") (class "Default")
      (node (ref "J16") (pin "10") (pinfunction "10_10") (pintype "passive"))
    )
    (net (code "232") (name "unconnected-(J16-Pad11)") (class "Default")
      (node (ref "J16") (pin "11") (pinfunction "11_11") (pintype "passive"))
    )
    (net (code "233") (name "unconnected-(J16-Pad12)") (class "Default")
      (node (ref "J16") (pin "12") (pinfunction "12_12") (pintype "passive"))
    )
    (net (code "234") (name "unconnected-(J16-Pad13)") (class "Default")
      (node (ref "J16") (pin "13") (pinfunction "13_13") (pintype "passive"))
    )
    (net (code "235") (name "unconnected-(J16-Pad14)") (class "Default")
      (node (ref "J16") (pin "14") (pinfunction "14_14") (pintype "passive"))
    )
    (net (code "236") (name "unconnected-(J16-Pad15)") (class "Default")
      (node (ref "J16") (pin "15") (pinfunction "15_15") (pintype "passive"))
    )
    (net (code "237") (name "unconnected-(J16-Pad16)") (class "Default")
      (node (ref "J16") (pin "16") (pinfunction "16_16") (pintype "passive"))
    )
    (net (code "238") (name "unconnected-(J17-Pad1)") (class "Default")
      (node (ref "J17") (pin "1") (pinfunction "1_1") (pintype "passive"))
    )
    (net (code "239") (name "unconnected-(J17-Pad2)") (class "Default")
      (node (ref "J17") (pin "2") (pinfunction "2_2") (pintype "passive"))
    )
    (net (code "240") (name "unconnected-(J17-Pad3)") (class "Default")
      (node (ref "J17") (pin "3") (pinfunction "3_3") (pintype "passive"))
    )
    (net (code "241") (name "unconnected-(J17-Pad4)") (class "Default")
      (node (ref "J17") (pin "4") (pinfunction "4_4") (pintype "passive"))
    )
    (net (code "242") (name "unconnected-(J17-Pad5)") (class "Default")
      (node (ref "J17") (pin "5") (pinfunction "5_5") (pintype "passive"))
    )
    (net (code "243") (name "unconnected-(J17-Pad6)") (class "Default")
      (node (ref "J17") (pin "6") (pinfunction "6_6") (pintype "passive"))
    )
    (net (code "244") (name "unconnected-(J17-Pad7)") (class "Default")
      (node (ref "J17") (pin "7") (pinfunction "7_7") (pintype "passive"))
    )
    (net (code "245") (name "unconnected-(J17-Pad8)") (class "Default")
      (node (ref "J17") (pin "8") (pinfunction "8_8") (pintype "passive"))
    )
    (net (code "246") (name "unconnected-(J17-Pad9)") (class "Default")
      (node (ref "J17") (pin "9") (pinfunction "9_9") (pintype "passive"))
    )
    (net (code "247") (name "unconnected-(J17-Pad10)") (class "Default")
      (node (ref "J17") (pin "10") (pinfunction "10_10") (pintype "passive"))
    )
    (net (code "248") (name "unconnected-(J17-Pad11)") (class "Default")
      (node (ref "J17") (pin "11") (pinfunction "11_11") (pintype "passive"))
    )
    (net (code "249") (name "unconnected-(J17-Pad12)") (class "Default")
      (node (ref "J17") (pin "12") (pinfunction "12_12") (pintype "passive"))
    )
    (net (code "250") (name "unconnected-(J17-Pad13)") (class "Default")
      (node (ref "J17") (pin "13") (pinfunction "13_13") (pintype "passive"))
    )
    (net (code "251") (name "unconnected-(J17-Pad14)") (class "Default")
      (node (ref "J17") (pin "14") (pinfunction "14_14") (pintype "passive"))
    )
    (net (code "252") (name "unconnected-(J17-Pad15)") (class "Default")
      (node (ref "J17") (pin "15") (pinfunction "15_15") (pintype "passive"))
    )
    (net (code "253") (name "unconnected-(J17-Pad16)") (class "Default")
      (node (ref "J17") (pin "16") (pinfunction "16_16") (pintype "passive"))
    )
    (net (code "254") (name "unconnected-(J18-Pad1)") (class "Default")
      (node (ref "J18") (pin "1") (pinfunction "1_1") (pintype "passive"))
    )
    (net (code "255") (name "unconnected-(J18-Pad2)") (class "Default")
      (node (ref "J18") (pin "2") (pinfunction "2_2") (pintype "passive"))
    )
    (net (code "256") (name "unconnected-(J18-Pad3)") (class "Default")
      (node (ref "J18") (pin "3") (pinfunction "3_3") (pintype "passive"))
    )
    (net (code "257") (name "unconnected-(J18-Pad4)") (class "Default")
      (node (ref "J18") (pin "4") (pinfunction "4_4") (pintype "passive"))
    )
    (net (code "258") (name "unconnected-(J18-Pad5)") (class "Default")
      (node (ref "J18") (pin "5") (pinfunction "5_5") (pintype "passive"))
    )
    (net (code "259") (name "unconnected-(J18-Pad6)") (class "Default")
      (node (ref "J18") (pin "6") (pinfunction "6_6") (pintype "passive"))
    )
    (net (code "260") (name "unconnected-(J18-Pad7)") (class "Default")
      (node (ref "J18") (pin "7") (pinfunction "7_7") (pintype "passive"))
    )
    (net (code "261") (name "unconnected-(J18-Pad8)") (class "Default")
      (node (ref "J18") (pin "8") (pinfunction "8_8") (pintype "passive"))
    )
    (net (code "262") (name "unconnected-(J18-Pad9)") (class "Default")
      (node (ref "J18") (pin "9") (pinfunction "9_9") (pintype "passive"))
    )
    (net (code "263") (name "unconnected-(J18-Pad10)") (class "Default")
      (node (ref "J18") (pin "10") (pinfunction "10_10") (pintype "passive"))
    )
    (net (code "264") (name "unconnected-(J18-Pad11)") (class "Default")
      (node (ref "J18") (pin "11") (pinfunction "11_11") (pintype "passive"))
    )
    (net (code "265") (name "unconnected-(J18-Pad12)") (class "Default")
      (node (ref "J18") (pin "12") (pinfunction "12_12") (pintype "passive"))
    )
    (net (code "266") (name "unconnected-(J18-Pad13)") (class "Default")
      (node (ref "J18") (pin "13") (pinfunction "13_13") (pintype "passive"))
    )
    (net (code "267") (name "unconnected-(J18-Pad14)") (class "Default")
      (node (ref "J18") (pin "14") (pinfunction "14_14") (pintype "passive"))
    )
    (net (code "268") (name "unconnected-(J18-Pad15)") (class "Default")
      (node (ref "J18") (pin "15") (pinfunction "15_15") (pintype "passive"))
    )
    (net (code "269") (name "unconnected-(J18-Pad16)") (class "Default")
      (node (ref "J18") (pin "16") (pinfunction "16_16") (pintype "passive"))
    )
    (net (code "270") (name "unconnected-(J19-Pad1)") (class "Default")
      (node (ref "J19") (pin "1") (pinfunction "1_1") (pintype "passive"))
    )
    (net (code "271") (name "unconnected-(J19-Pad2)") (class "Default")
      (node (ref "J19") (pin "2") (pinfunction "2_2") (pintype "passive"))
    )
    (net (code "272") (name "unconnected-(J19-Pad3)") (class "Default")
      (node (ref "J19") (pin "3") (pinfunction "3_3") (pintype "passive"))
    )
    (net (code "273") (name "unconnected-(J19-Pad4)") (class "Default")
      (node (ref "J19") (pin "4") (pinfunction "4_4") (pintype "passive"))
    )
    (net (code "274") (name "unconnected-(J19-Pad5)") (class "Default")
      (node (ref "J19") (pin "5") (pinfunction "5_5") (pintype "passive"))
    )
    (net (code "275") (name "unconnected-(J19-Pad6)") (class "Default")
      (node (ref "J19") (pin "6") (pinfunction "6_6") (pintype "passive"))
    )
    (net (code "276") (name "unconnected-(J19-Pad7)") (class "Default")
      (node (ref "J19") (pin "7") (pinfunction "7_7") (pintype "passive"))
    )
    (net (code "277") (name "unconnected-(J19-Pad8)") (class "Default")
      (node (ref "J19") (pin "8") (pinfunction "8_8") (pintype "passive"))
    )
    (net (code "278") (name "unconnected-(J19-Pad9)") (class "Default")
      (node (ref "J19") (pin "9") (pinfunction "9_9") (pintype "passive"))
    )
    (net (code "279") (name "unconnected-(J19-Pad10)") (class "Default")
      (node (ref "J19") (pin "10") (pinfunction "10_10") (pintype "passive"))
    )
    (net (code "280") (name "unconnected-(J19-Pad11)") (class "Default")
      (node (ref "J19") (pin "11") (pinfunction "11_11") (pintype "passive"))
    )
    (net (code "281") (name "unconnected-(J19-Pad12)") (class "Default")
      (node (ref "J19") (pin "12") (pinfunction "12_12") (pintype "passive"))
    )
    (net (code "282") (name "unconnected-(J19-Pad13)") (class "Default")
      (node (ref "J19") (pin "13") (pinfunction "13_13") (pintype "passive"))
    )
    (net (code "283") (name "unconnected-(J19-Pad14)") (class "Default")
      (node (ref "J19") (pin "14") (pinfunction "14_14") (pintype "passive"))
    )
    (net (code "284") (name "unconnected-(J19-Pad15)") (class "Default")
      (node (ref "J19") (pin "15") (pinfunction "15_15") (pintype "passive"))
    )
    (net (code "285") (name "unconnected-(J19-Pad16)") (class "Default")
      (node (ref "J19") (pin "16") (pinfunction "16_16") (pintype "passive"))
    )
    (net (code "286") (name "unconnected-(J20-Pad1)") (class "Default")
      (node (ref "J20") (pin "1") (pinfunction "1_1") (pintype "passive"))
    )
    (net (code "287") (name "unconnected-(J20-Pad2)") (class "Default")
      (node (ref "J20") (pin "2") (pinfunction "2_2") (pintype "passive"))
    )
    (net (code "288") (name "unconnected-(J20-Pad3)") (class "Default")
      (node (ref "J20") (pin "3") (pinfunction "3_3") (pintype "passive"))
    )
    (net (code "289") (name "unconnected-(J20-Pad4)") (class "Default")
      (node (ref "J20") (pin "4") (pinfunction "4_4") (pintype "passive"))
    )
    (net (code "290") (name "unconnected-(J20-Pad5)") (class "Default")
      (node (ref "J20") (pin "5") (pinfunction "5_5") (pintype "passive"))
    )
    (net (code "291") (name "unconnected-(J20-Pad6)") (class "Default")
      (node (ref "J20") (pin "6") (pinfunction "6_6") (pintype "passive"))
    )
    (net (code "292") (name "unconnected-(J20-Pad7)") (class "Default")
      (node (ref "J20") (pin "7") (pinfunction "7_7") (pintype "passive"))
    )
    (net (code "293") (name "unconnected-(J20-Pad8)") (class "Default")
      (node (ref "J20") (pin "8") (pinfunction "8_8") (pintype "passive"))
    )
    (net (code "294") (name "unconnected-(J20-Pad9)") (class "Default")
      (node (ref "J20") (pin "9") (pinfunction "9_9") (pintype "passive"))
    )
    (net (code "295") (name "unconnected-(J20-Pad10)") (class "Default")
      (node (ref "J20") (pin "10") (pinfunction "10_10") (pintype "passive"))
    )
    (net (code "296") (name "unconnected-(J20-Pad11)") (class "Default")
      (node (ref "J20") (pin "11") (pinfunction "11_11") (pintype "passive"))
    )
    (net (code "297") (name "unconnected-(J20-Pad12)") (class "Default")
      (node (ref "J20") (pin "12") (pinfunction "12_12") (pintype "passive"))
    )
    (net (code "298") (name "unconnected-(J20-Pad13)") (class "Default")
      (node (ref "J20") (pin "13") (pinfunction "13_13") (pintype "passive"))
    )
    (net (code "299") (name "unconnected-(J20-Pad14)") (class "Default")
      (node (ref "J20") (pin "14") (pinfunction "14_14") (pintype "passive"))
    )
    (net (code "300") (name "unconnected-(J20-Pad15)") (class "Default")
      (node (ref "J20") (pin "15") (pinfunction "15_15") (pintype "passive"))
    )
    (net (code "301") (name "unconnected-(J20-Pad16)") (class "Default")
      (node (ref "J20") (pin "16") (pinfunction "16_16") (pintype "passive"))
    )
    (net (code "302") (name "unconnected-(J21-Pad1)") (class "Default")
      (node (ref "J21") (pin "1") (pinfunction "1_1") (pintype "passive"))
    )
    (net (code "303") (name "unconnected-(J21-Pad2)") (class "Default")
      (node (ref "J21") (pin "2") (pinfunction "2_2") (pintype "passive"))
    )
    (net (code "304") (name "unconnected-(J21-Pad3)") (class "Default")
      (node (ref "J21") (pin "3") (pinfunction "3_3") (pintype "passive"))
    )
    (net (code "305") (name "unconnected-(J21-Pad4)") (class "Default")
      (node (ref "J21") (pin "4") (pinfunction "4_4") (pintype "passive"))
    )
    (net (code "306") (name "unconnected-(J22-Pad1)") (class "Default")
      (node (ref "J22") (pin "1") (pinfunction "1_1") (pintype "passive"))
    )
    (net (code "307") (name "unconnected-(J22-Pad2)") (class "Default")
      (node (ref "J22") (pin "2") (pinfunction "2_2") (pintype "passive"))
    )
    (net (code "308") (name "unconnected-(J22-Pad3)") (class "Default")
      (node (ref "J22") (pin "3") (pinfunction "3_3") (pintype "passive"))
    )
    (net (code "309") (name "unconnected-(J22-Pad4)") (class "Default")
      (node (ref "J22") (pin "4") (pinfunction "4_4") (pintype "passive"))
    )
    (net (code "310") (name "unconnected-(J25-Pad1)") (class "Default")
      (node (ref "J25") (pin "1") (pinfunction "1_1") (pintype "passive"))
    )
    (net (code "311") (name "unconnected-(J28-Pad1)") (class "Default")
      (node (ref "J28") (pin "1") (pinfunction "1_1") (pintype "passive"))
    )
    (net (code "312") (name "unconnected-(J28-Pad2)") (class "Default")
      (node (ref "J28") (pin "2") (pinfunction "2_2") (pintype "passive"))
    )
    (net (code "313") (name "unconnected-(J28-Pad3)") (class "Default")
      (node (ref "J28") (pin "3") (pinfunction "3_3") (pintype "passive"))
    )
    (net (code "314") (name "unconnected-(J28-Pad4)") (class "Default")
      (node (ref "J28") (pin "4") (pinfunction "4_4") (pintype "passive"))
    )
  )
)
